# project.net
KiCad netlist of a schematic drawn in EAGLE
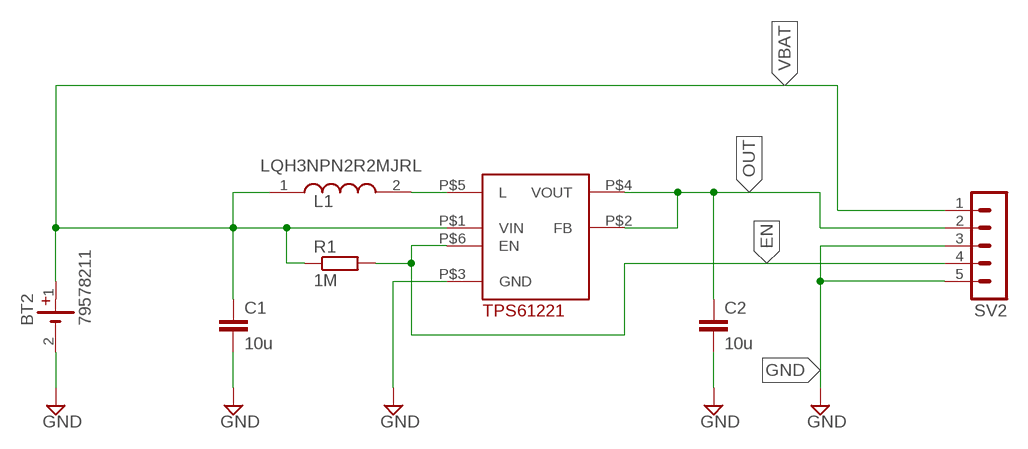
[diagram p0: schematic, sheet 1]

(export (version "E")
  (design (tool "Eeschema 10.0.6"))
  (components
    (comp (ref "BT2")
      (value "79578211")
      (footprint "eagle-import:79578211")
      (fields
        (field (name "DIGIKEY_PART_NO") "732-12330-ND")
        (field (name "MANUFACTURER") "Wurth Electronics Inc.")
        (field (name "CREATED_BY") "PCBLayout.com")
      )
      (libsource (lib "eagle-import") (part "79578211"))
    )
    (comp (ref "C1")
      (value "10u")
      (footprint "eagle-import:C0805K")
      (libsource (lib "eagle-import") (part "C-EUC0805K"))
    )
    (comp (ref "C2")
      (value "10u")
      (footprint "eagle-import:C0805K")
      (libsource (lib "eagle-import") (part "C-EUC0805K"))
    )
    (comp (ref "L1")
      (value "LQH3NPN2R2MJRL")
      (footprint "eagle-import:INDPM3030X120N")
      (fields (field (name "MOUSER_PART_NUMBER") "81-LQH3NPN2R2MJRL"))
      (libsource (lib "eagle-import") (part "LQH3NPN2R2MJRL"))
    )
    (comp (ref "R1")
      (value "1M")
      (footprint "eagle-import:R0805")
      (libsource (lib "eagle-import") (part "R-EU_R0805"))
    )
    (comp (ref "SV2")
      (value "MA05-1")
      (footprint "eagle-import:MA05-1")
      (libsource (lib "eagle-import") (part "MA05-1"))
    )
    (comp (ref "U$1")
      (value "TPS61221")
      (footprint "eagle-import:TPS61221")
      (fields (field (name "MF") "Texas Instruments"))
      (libsource (lib "eagle-import") (part "TPS61221"))
    )
  )
  (nets
    (net (code "1") (name "EN") (class "Default")
      (node (ref "R1") (pin "2") (pinfunction "2_2") (pintype "passive"))
      (node (ref "SV2") (pin "4") (pinfunction "4_4") (pintype "passive"))
      (node (ref "U$1") (pin "P$6") (pinfunction "EN_P$6") (pintype "bidirectional"))
    )
    (net (code "2") (name "GND") (class "Default")
      (node (ref "BT2") (pin "2") (pinfunction "-_2") (pintype "passive"))
      (node (ref "C1") (pin "2") (pinfunction "2_2") (pintype "passive"))
      (node (ref "C2") (pin "2") (pinfunction "2_2") (pintype "passive"))
      (node (ref "SV2") (pin "3") (pinfunction "3_3") (pintype "passive"))
      (node (ref "SV2") (pin "5") (pinfunction "5_5") (pintype "passive"))
      (node (ref "U$1") (pin "P$3") (pinfunction "GND_P$3") (pintype "bidirectional"))
    )
    (net (code "3") (name "Net-(U$1-L)") (class "Default")
      (node (ref "L1") (pin "2") (pinfunction "2_2") (pintype "bidirectional"))
      (node (ref "U$1") (pin "P$5") (pinfunction "L_P$5") (pintype "bidirectional"))
    )
    (net (code "4") (name "OUT") (class "Default")
      (node (ref "C2") (pin "1") (pinfunction "1_1") (pintype "passive"))
      (node (ref "SV2") (pin "2") (pinfunction "2_2") (pintype "passive"))
      (node (ref "U$1") (pin "P$2") (pinfunction "FB_P$2") (pintype "bidirectional"))
      (node (ref "U$1") (pin "P$4") (pinfunction "VOUT_P$4") (pintype "bidirectional"))
    )
    (net (code "5") (name "VBAT") (class "Default")
      (node (ref "BT2") (pin "1") (pinfunction "+_1") (pintype "passive"))
      (node (ref "C1") (pin "1") (pinfunction "1_1") (pintype "passive"))
      (node (ref "L1") (pin "1") (pinfunction "1_1") (pintype "bidirectional"))
      (node (ref "R1") (pin "1") (pinfunction "1_1") (pintype "passive"))
      (node (ref "SV2") (pin "1") (pinfunction "1_1") (pintype "passive"))
      (node (ref "U$1") (pin "P$1") (pinfunction "VIN_P$1") (pintype "bidirectional"))
    )
  )
)
